# 01_Power_Suppy.net
KiCad netlist of a schematic drawn in Altium Designer
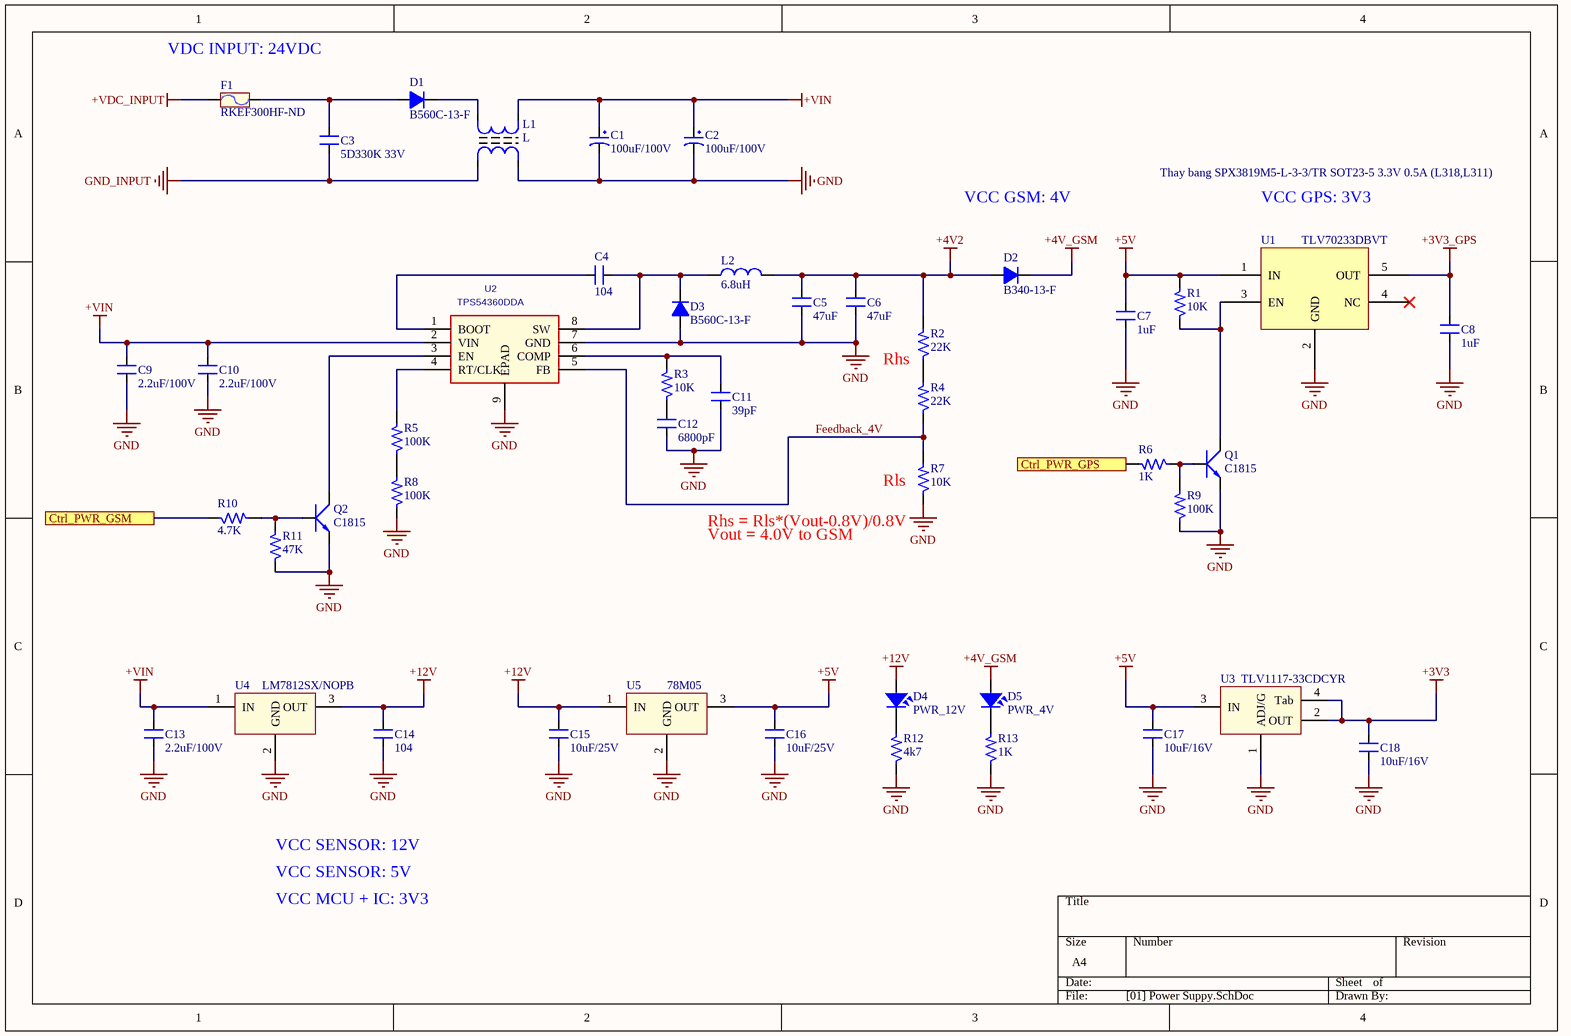
[diagram p0: [01] Power Suppy.SchDoc]

(export (version "E")
  (design (tool "Eeschema 10.0.6"))
  (components
    (comp (ref "C1")
      (value "100uF/100V")
      (footprint "CP1.5/3.4")
      (description "Cap 100uF/35V - 470uF/16V")
      (libsource (lib "syhaunguyen") (part "CP3"))
    )
    (comp (ref "C2")
      (value "100uF/100V")
      (footprint "CP1.5/3.4")
      (description "Cap 100uF/35V - 470uF/16V")
      (libsource (lib "syhaunguyen") (part "CP3"))
    )
    (comp (ref "C3")
      (value "5D330K 33V")
      (footprint "CN2")
      (fields (field (name "DESIGNED BY") "VanDungEvn"))
      (libsource (lib "GPS_Traking_V1_1") (part "CN"))
    )
    (comp (ref "C4")
      (value "104")
      (footprint "C0603 SMT")
      (description "Cap SMD")
      (libsource (lib "GPS_Traking_V1_1") (part "CM_1"))
    )
    (comp (ref "C5")
      (value "47uF")
      (footprint "SM-1210")
      (description "Cap SMD")
      (libsource (lib "GPS_Traking_V1_1") (part "CM_1"))
    )
    (comp (ref "C6")
      (value "47uF")
      (footprint "SM-1210")
      (description "Cap SMD")
      (libsource (lib "GPS_Traking_V1_1") (part "CM_1"))
    )
    (comp (ref "C7")
      (value "1uF")
      (footprint "CAP_0805")
      (description "Cap SMD")
      (libsource (lib "GPS_Traking_V1_1") (part "CM_1"))
    )
    (comp (ref "C8")
      (value "1uF")
      (footprint "CAP_0805")
      (description "Cap SMD")
      (libsource (lib "GPS_Traking_V1_1") (part "CM_1"))
    )
    (comp (ref "C9")
      (value "2.2uF/100V")
      (footprint "SM-1210")
      (description "CAP CER 2.2UF 100V X7R 1210  445-4498-2-ND")
      (libsource (lib "GPS_Traking_V1_1") (part "CM"))
    )
    (comp (ref "C10")
      (value "2.2uF/100V")
      (footprint "SM-1210")
      (description "CAP CER 2.2UF 100V X7R 1210  445-4498-2-ND")
      (libsource (lib "GPS_Traking_V1_1") (part "CM"))
    )
    (comp (ref "C11")
      (value "39pF")
      (footprint "CAP_0805")
      (description "Cap SMD")
      (libsource (lib "GPS_Traking_V1_1") (part "CM_1"))
    )
    (comp (ref "C12")
      (value "6800pF")
      (footprint "CAP_0805")
      (description "Cap SMD")
      (libsource (lib "GPS_Traking_V1_1") (part "CM_1"))
    )
    (comp (ref "C13")
      (value "2.2uF/100V")
      (footprint "SM-1210")
      (description "CAP CER 2.2UF 100V X7R 1210  445-4498-2-ND")
      (libsource (lib "GPS_Traking_V1_1") (part "CM"))
    )
    (comp (ref "C14")
      (value "104")
      (footprint "CAP_0805")
      (description "Cap SMD")
      (libsource (lib "GPS_Traking_V1_1") (part "CM_1"))
    )
    (comp (ref "C15")
      (value "10uF/25V")
      (footprint "CAP_0805")
      (description "Cap SMD")
      (libsource (lib "GPS_Traking_V1_1") (part "CM_1"))
    )
    (comp (ref "C16")
      (value "10uF/25V")
      (footprint "CAP_0805")
      (description "Cap SMD")
      (libsource (lib "GPS_Traking_V1_1") (part "CM_1"))
    )
    (comp (ref "C17")
      (value "10uF/16V")
      (footprint "CAP_0805")
      (description "Cap SMD")
      (libsource (lib "GPS_Traking_V1_1") (part "CM_1"))
    )
    (comp (ref "C18")
      (value "10uF/16V")
      (footprint "CAP_0805")
      (description "Cap SMD")
      (libsource (lib "GPS_Traking_V1_1") (part "CM_1"))
    )
    (comp (ref "D1")
      (value "B560C-13-F")
      (footprint "DO-214AB SMC")
      (description "DIODE SCHOTTKY 60V 5A SMC")
      (libsource (lib "GPS_Traking_V1_1") (part "D5A"))
    )
    (comp (ref "D2")
      (value "B340-13-F")
      (footprint "DO-214AB SMA")
      (description "DIODE SCHOTTKY 40V 3A SMC")
      (libsource (lib "GPS_Traking_V1_1") (part "D1A"))
    )
    (comp (ref "D3")
      (value "B560C-13-F")
      (footprint "DO-214AB SMC")
      (description "DIODE SCHOTTKY 60V 5A SMC")
      (libsource (lib "GPS_Traking_V1_1") (part "D5A"))
    )
    (comp (ref "D4")
      (value "PWR_12V")
      (footprint "LED-0805-Yellow")
      (description "LED Single colour Green and Red")
      (libsource (lib "GPS_Traking_V1_1") (part "LED"))
    )
    (comp (ref "D5")
      (value "PWR_4V")
      (footprint "LED-0805-Green")
      (description "LED Single colour Green and Red")
      (libsource (lib "GPS_Traking_V1_1") (part "LED"))
    )
    (comp (ref "F1")
      (value "RKEF300HF-ND")
      (footprint "FUSE2")
      (description "PTC RESET FUSE 60V 3A RADIAL")
      (fields (field (name "DESIGNED BY") "VanDungEvn"))
      (libsource (lib "GPS_Traking_V1_1") (part "Fuse"))
    )
    (comp (ref "L1")
      (value "L")
      (footprint "L2 UF9.8")
      (description "Inductor")
      (fields (field (name "DESIGNED BY") "VanDungEvn"))
      (libsource (lib "GPS_Traking_V1_1") (part "L2x220"))
    )
    (comp (ref "L2")
      (value "6.8uH")
      (footprint "L01 SMD 12*12*6")
      (description "FIXED IND 6.2UH 5.7A 22.4 MOHM")
      (libsource (lib "GPS_Traking_V1_1") (part "L1"))
    )
    (comp (ref "Q1")
      (value "C1815")
      (footprint "SOT23B")
      (description "NPN 600mW, ECB")
      (libsource (lib "GPS_Traking_V1_1") (part "C1815"))
    )
    (comp (ref "Q2")
      (value "C1815")
      (footprint "SOT23B")
      (description "NPN 600mW, ECB")
      (libsource (lib "GPS_Traking_V1_1") (part "C1815"))
    )
    (comp (ref "R1")
      (value "10K")
      (footprint "RES-SMD-0805")
      (description "Resistor SMD")
      (libsource (lib "GPS_Traking_V1_1") (part "RM"))
    )
    (comp (ref "R2")
      (value "22K")
      (footprint "RES-SMD-0805")
      (description "Resistor SMD")
      (libsource (lib "GPS_Traking_V1_1") (part "RM"))
    )
    (comp (ref "R3")
      (value "10K")
      (footprint "RES-SMD-0805")
      (description "Resistor SMD")
      (libsource (lib "GPS_Traking_V1_1") (part "RM"))
    )
    (comp (ref "R4")
      (value "22K")
      (footprint "RES-SMD-0805")
      (description "Resistor SMD")
      (libsource (lib "GPS_Traking_V1_1") (part "RM"))
    )
    (comp (ref "R5")
      (value "100K")
      (footprint "RES-SMD-0805")
      (description "Resistor SMD")
      (libsource (lib "GPS_Traking_V1_1") (part "RM"))
    )
    (comp (ref "R6")
      (value "1K")
      (footprint "RES-SMD-0805")
      (description "Resistor SMD")
      (libsource (lib "GPS_Traking_V1_1") (part "RM"))
    )
    (comp (ref "R7")
      (value "10K")
      (footprint "RES-SMD-0805")
      (description "Resistor SMD")
      (libsource (lib "GPS_Traking_V1_1") (part "RM"))
    )
    (comp (ref "R8")
      (value "100K")
      (footprint "RES-SMD-0805")
      (description "Resistor SMD")
      (libsource (lib "GPS_Traking_V1_1") (part "RM"))
    )
    (comp (ref "R9")
      (value "100K")
      (footprint "RES-SMD-0805")
      (description "Resistor SMD")
      (libsource (lib "GPS_Traking_V1_1") (part "RM"))
    )
    (comp (ref "R10")
      (value "4.7K")
      (footprint "RES-SMD-0805")
      (description "Resistor SMD")
      (libsource (lib "GPS_Traking_V1_1") (part "RM"))
    )
    (comp (ref "R11")
      (value "47K")
      (footprint "RES-SMD-0805")
      (description "Resistor SMD")
      (libsource (lib "GPS_Traking_V1_1") (part "RM"))
    )
    (comp (ref "R12")
      (value "4k7")
      (footprint "RES-SMD-0805")
      (description "Resistor SMD")
      (libsource (lib "GPS_Traking_V1_1") (part "RM"))
    )
    (comp (ref "R13")
      (value "1K")
      (footprint "RES-SMD-0805")
      (description "Resistor SMD")
      (libsource (lib "GPS_Traking_V1_1") (part "RM"))
    )
    (comp (ref "U1")
      (value "TLV70233DBVT")
      (footprint "TLV70233_3.3V")
      (libsource (lib "GPS_Traking_V1_1") (part "TLV70233_3.3V"))
    )
    (comp (ref "U2")
      (value "TPS54360DDA")
      (footprint "DDA8_3P1X2P4-M")
      (description "REG BUCK SPLIT RAIL 8SOPWRPAD")
      (libsource (lib "GPS_Traking_V1_1") (part "TPS54360DDA"))
    )
    (comp (ref "U3")
      (value "TLV1117-33CDCYR")
      (footprint "SOT223-4N")
      (description "3v3")
      (libsource (lib "GPS_Traking_V1_1") (part "LM1117"))
    )
    (comp (ref "U4")
      (value "LM7812SX/NOPB")
      (footprint "TO-263-4")
      (libsource (lib "GPS_Traking_V1_1") (part "LM78xx_1"))
    )
    (comp (ref "U5")
      (value "78M05")
      (footprint "TO252-3L")
      (description "On ap +, from + 5 to + 24VDC")
      (libsource (lib "GPS_Traking_V1_1") (part "LM78xx"))
    )
  )
  (nets
    (net (code "1") (name "+3V3") (class "Default")
      (node (ref "C18") (pin "2") (pinfunction "2_2") (pintype "passive"))
      (node (ref "U3") (pin "2") (pinfunction "OUT_2") (pintype "passive"))
      (node (ref "U3") (pin "4") (pinfunction "Tab_4") (pintype "passive"))
    )
    (net (code "2") (name "+3V3_GPS") (class "Default")
      (node (ref "C8") (pin "2") (pinfunction "2_2") (pintype "passive"))
      (node (ref "U1") (pin "5") (pinfunction "OUT_5") (pintype "passive"))
    )
    (net (code "3") (name "+4V2") (class "Default")
      (node (ref "C5") (pin "2") (pinfunction "2_2") (pintype "passive"))
      (node (ref "C6") (pin "2") (pinfunction "2_2") (pintype "passive"))
      (node (ref "D2") (pin "1") (pinfunction "A_1") (pintype "passive"))
      (node (ref "L2") (pin "2") (pinfunction "2_2") (pintype "passive"))
      (node (ref "R2") (pin "2") (pinfunction "2_2") (pintype "passive"))
    )
    (net (code "4") (name "+4V_GSM") (class "Default")
      (node (ref "D2") (pin "2") (pinfunction "K_2") (pintype "passive"))
      (node (ref "D5") (pin "1") (pinfunction "1_1") (pintype "passive"))
    )
    (net (code "5") (name "+5V") (class "Default")
      (node (ref "C16") (pin "2") (pinfunction "2_2") (pintype "passive"))
      (node (ref "C17") (pin "2") (pinfunction "2_2") (pintype "passive"))
      (node (ref "C7") (pin "2") (pinfunction "2_2") (pintype "passive"))
      (node (ref "R1") (pin "2") (pinfunction "2_2") (pintype "passive"))
      (node (ref "U1") (pin "1") (pinfunction "IN_1") (pintype "passive"))
      (node (ref "U3") (pin "3") (pinfunction "IN_3") (pintype "passive"))
      (node (ref "U5") (pin "3") (pinfunction "OUT_3") (pintype "passive"))
    )
    (net (code "6") (name "+12V") (class "Default")
      (node (ref "C14") (pin "2") (pinfunction "2_2") (pintype "passive"))
      (node (ref "C15") (pin "2") (pinfunction "2_2") (pintype "passive"))
      (node (ref "D4") (pin "1") (pinfunction "1_1") (pintype "passive"))
      (node (ref "U4") (pin "3") (pinfunction "OUT_3") (pintype "passive"))
      (node (ref "U5") (pin "1") (pinfunction "IN_1") (pintype "passive"))
    )
    (net (code "7") (name "+VDC_INPUT") (class "Default")
      (node (ref "F1") (pin "1") (pinfunction "1_1") (pintype "passive"))
    )
    (net (code "8") (name "+VIN") (class "Default")
      (node (ref "C1") (pin "1") (pinfunction "1_1") (pintype "passive"))
      (node (ref "C10") (pin "2") (pinfunction "2_2") (pintype "passive"))
      (node (ref "C13") (pin "2") (pinfunction "2_2") (pintype "passive"))
      (node (ref "C2") (pin "1") (pinfunction "1_1") (pintype "passive"))
      (node (ref "C9") (pin "2") (pinfunction "2_2") (pintype "passive"))
      (node (ref "L1") (pin "3") (pinfunction "3_3") (pintype "passive"))
      (node (ref "U2") (pin "2") (pinfunction "VIN_2") (pintype "passive"))
      (node (ref "U4") (pin "1") (pinfunction "IN_1") (pintype "passive"))
    )
    (net (code "9") (name "/Ctrl_PWR_GPS") (class "Default")
      (node (ref "R6") (pin "2") (pinfunction "2_2") (pintype "passive"))
    )
    (net (code "10") (name "/Ctrl_PWR_GSM") (class "Default")
      (node (ref "R10") (pin "1") (pinfunction "1_1") (pintype "passive"))
    )
    (net (code "11") (name "/Feedback_4V") (class "Default")
      (node (ref "R4") (pin "1") (pinfunction "1_1") (pintype "passive"))
      (node (ref "R7") (pin "2") (pinfunction "2_2") (pintype "passive"))
      (node (ref "U2") (pin "5") (pinfunction "FB_5") (pintype "passive"))
    )
    (net (code "12") (name "GND") (class "Default")
      (node (ref "C1") (pin "2") (pinfunction "2_2") (pintype "passive"))
      (node (ref "C10") (pin "1") (pinfunction "1_1") (pintype "passive"))
      (node (ref "C11") (pin "1") (pinfunction "1_1") (pintype "passive"))
      (node (ref "C12") (pin "1") (pinfunction "1_1") (pintype "passive"))
      (node (ref "C13") (pin "1") (pinfunction "1_1") (pintype "passive"))
      (node (ref "C14") (pin "1") (pinfunction "1_1") (pintype "passive"))
      (node (ref "C15") (pin "1") (pinfunction "1_1") (pintype "passive"))
      (node (ref "C16") (pin "1") (pinfunction "1_1") (pintype "passive"))
      (node (ref "C17") (pin "1") (pinfunction "1_1") (pintype "passive"))
      (node (ref "C18") (pin "1") (pinfunction "1_1") (pintype "passive"))
      (node (ref "C2") (pin "2") (pinfunction "2_2") (pintype "passive"))
      (node (ref "C5") (pin "1") (pinfunction "1_1") (pintype "passive"))
      (node (ref "C6") (pin "1") (pinfunction "1_1") (pintype "passive"))
      (node (ref "C7") (pin "1") (pinfunction "1_1") (pintype "passive"))
      (node (ref "C8") (pin "1") (pinfunction "1_1") (pintype "passive"))
      (node (ref "C9") (pin "1") (pinfunction "1_1") (pintype "passive"))
      (node (ref "D3") (pin "1") (pinfunction "A_1") (pintype "passive"))
      (node (ref "L1") (pin "2") (pinfunction "2_2") (pintype "passive"))
      (node (ref "Q1") (pin "1") (pinfunction "E_1") (pintype "passive"))
      (node (ref "Q2") (pin "1") (pinfunction "E_1") (pintype "passive"))
      (node (ref "R11") (pin "1") (pinfunction "1_1") (pintype "passive"))
      (node (ref "R12") (pin "1") (pinfunction "1_1") (pintype "passive"))
      (node (ref "R13") (pin "1") (pinfunction "1_1") (pintype "passive"))
      (node (ref "R7") (pin "1") (pinfunction "1_1") (pintype "passive"))
      (node (ref "R8") (pin "1") (pinfunction "1_1") (pintype "passive"))
      (node (ref "R9") (pin "1") (pinfunction "1_1") (pintype "passive"))
      (node (ref "U1") (pin "2") (pinfunction "GND_2") (pintype "power_in"))
      (node (ref "U2") (pin "7") (pinfunction "GND_7") (pintype "passive"))
      (node (ref "U2") (pin "9") (pinfunction "EPAD_9") (pintype "passive"))
      (node (ref "U3") (pin "1") (pinfunction "ADJ/G_1") (pintype "passive"))
      (node (ref "U4") (pin "2") (pinfunction "GND_2") (pintype "passive"))
      (node (ref "U5") (pin "2") (pinfunction "GND_2") (pintype "passive"))
    )
    (net (code "13") (name "GND_INPUT") (class "Default")
      (node (ref "C3") (pin "1") (pinfunction "1_1") (pintype "passive"))
      (node (ref "L1") (pin "1") (pinfunction "1_1") (pintype "passive"))
    )
    (net (code "14") (name "Net-(C12-Pad2)") (class "Default")
      (node (ref "C12") (pin "2") (pinfunction "2_2") (pintype "passive"))
      (node (ref "R3") (pin "1") (pinfunction "1_1") (pintype "passive"))
    )
    (net (code "15") (name "Net-(D1-A)") (class "Default")
      (node (ref "C3") (pin "2") (pinfunction "2_2") (pintype "passive"))
      (node (ref "D1") (pin "1") (pinfunction "A_1") (pintype "passive"))
      (node (ref "F1") (pin "2") (pinfunction "2_2") (pintype "passive"))
    )
    (net (code "16") (name "Net-(D1-K)") (class "Default")
      (node (ref "D1") (pin "2") (pinfunction "K_2") (pintype "passive"))
      (node (ref "L1") (pin "4") (pinfunction "4_4") (pintype "passive"))
    )
    (net (code "17") (name "Net-(D3-K)") (class "Default")
      (node (ref "C4") (pin "2") (pinfunction "2_2") (pintype "passive"))
      (node (ref "D3") (pin "2") (pinfunction "K_2") (pintype "passive"))
      (node (ref "L2") (pin "1") (pinfunction "1_1") (pintype "passive"))
      (node (ref "U2") (pin "8") (pinfunction "SW_8") (pintype "passive"))
    )
    (net (code "18") (name "Net-(D4-Pad2)") (class "Default")
      (node (ref "D4") (pin "2") (pinfunction "2_2") (pintype "passive"))
      (node (ref "R12") (pin "2") (pinfunction "2_2") (pintype "passive"))
    )
    (net (code "19") (name "Net-(D5-Pad2)") (class "Default")
      (node (ref "D5") (pin "2") (pinfunction "2_2") (pintype "passive"))
      (node (ref "R13") (pin "2") (pinfunction "2_2") (pintype "passive"))
    )
    (net (code "20") (name "Net-(Q1-B)") (class "Default")
      (node (ref "Q1") (pin "3") (pinfunction "B_3") (pintype "passive"))
      (node (ref "R6") (pin "1") (pinfunction "1_1") (pintype "passive"))
      (node (ref "R9") (pin "2") (pinfunction "2_2") (pintype "passive"))
    )
    (net (code "21") (name "Net-(Q1-C)") (class "Default")
      (node (ref "Q1") (pin "2") (pinfunction "C_2") (pintype "passive"))
      (node (ref "R1") (pin "1") (pinfunction "1_1") (pintype "passive"))
      (node (ref "U1") (pin "3") (pinfunction "EN_3") (pintype "passive"))
    )
    (net (code "22") (name "Net-(Q2-B)") (class "Default")
      (node (ref "Q2") (pin "3") (pinfunction "B_3") (pintype "passive"))
      (node (ref "R10") (pin "2") (pinfunction "2_2") (pintype "passive"))
      (node (ref "R11") (pin "2") (pinfunction "2_2") (pintype "passive"))
    )
    (net (code "23") (name "Net-(Q2-C)") (class "Default")
      (node (ref "Q2") (pin "2") (pinfunction "C_2") (pintype "passive"))
      (node (ref "U2") (pin "3") (pinfunction "EN_3") (pintype "passive"))
    )
    (net (code "24") (name "Net-(R2-Pad1)") (class "Default")
      (node (ref "R2") (pin "1") (pinfunction "1_1") (pintype "passive"))
      (node (ref "R4") (pin "2") (pinfunction "2_2") (pintype "passive"))
    )
    (net (code "25") (name "Net-(R5-Pad1)") (class "Default")
      (node (ref "R5") (pin "1") (pinfunction "1_1") (pintype "passive"))
      (node (ref "R8") (pin "2") (pinfunction "2_2") (pintype "passive"))
    )
    (net (code "26") (name "Net-(U2-BOOT)") (class "Default")
      (node (ref "C4") (pin "1") (pinfunction "1_1") (pintype "passive"))
      (node (ref "U2") (pin "1") (pinfunction "BOOT_1") (pintype "passive"))
    )
    (net (code "27") (name "Net-(U2-COMP)") (class "Default")
      (node (ref "C11") (pin "2") (pinfunction "2_2") (pintype "passive"))
      (node (ref "R3") (pin "2") (pinfunction "2_2") (pintype "passive"))
      (node (ref "U2") (pin "6") (pinfunction "COMP_6") (pintype "passive"))
    )
    (net (code "28") (name "Net-(U2-RT{slash}CLK)") (class "Default")
      (node (ref "R5") (pin "2") (pinfunction "2_2") (pintype "passive"))
      (node (ref "U2") (pin "4") (pinfunction "RT/CLK_4") (pintype "passive"))
    )
    (net (code "29") (name "unconnected-(U1-NC-Pad4)") (class "Default")
      (node (ref "U1") (pin "4") (pinfunction "NC_4") (pintype "passive+no_connect"))
    )
  )
)
